# uc_ctrl.net
KiCad netlist of a schematic drawn in EAGLE
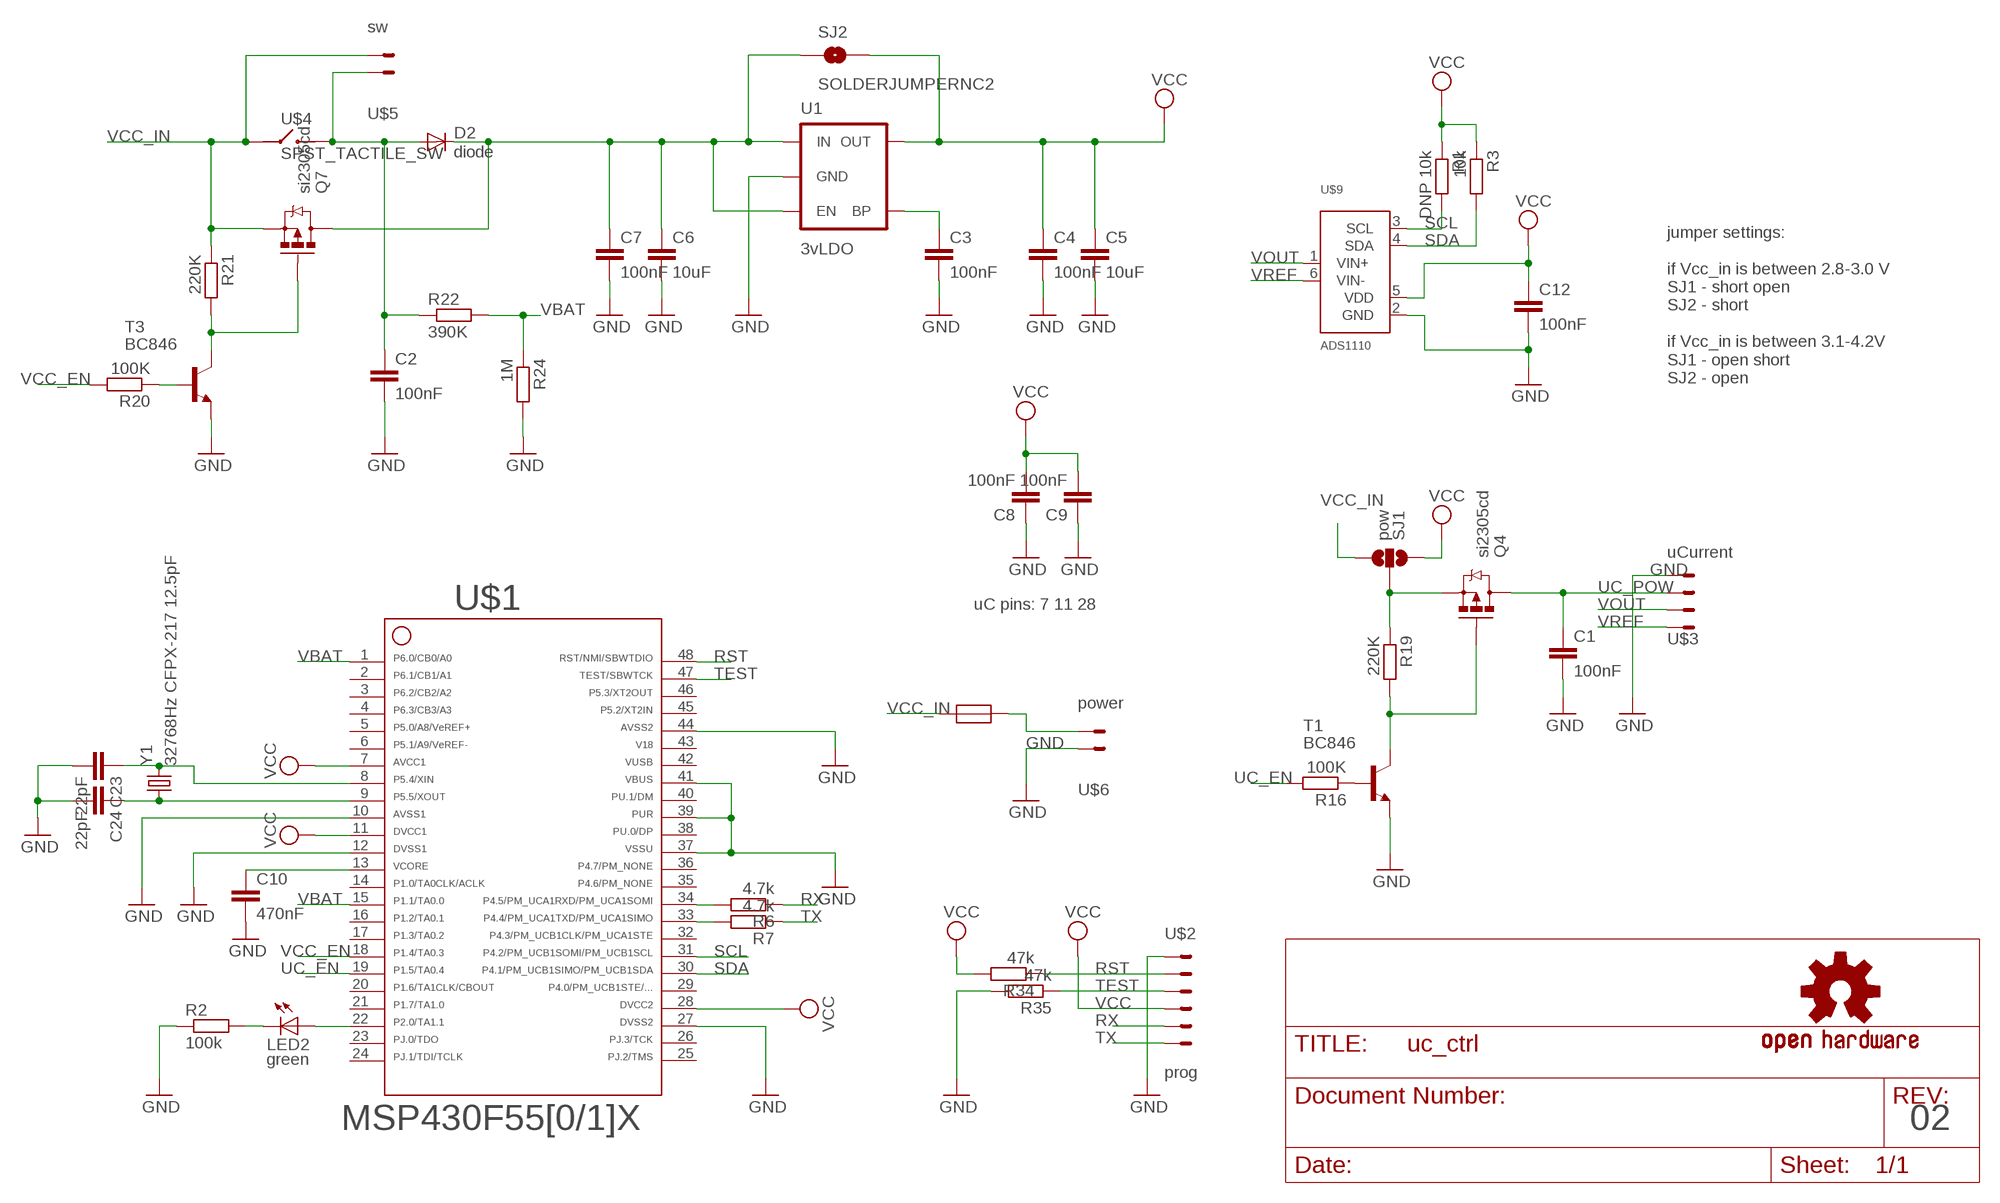
[diagram p0: schematic, sheet 1]

(export (version "E")
  (design (tool "Eeschema 10.0.6"))
  (components
    (comp (ref "C1")
      (value "100nF")
      (footprint "eagle-import:C0805")
      (libsource (lib "eagle-import") (part "C-EUC0805"))
    )
    (comp (ref "C2")
      (value "100nF")
      (footprint "eagle-import:C0805")
      (libsource (lib "eagle-import") (part "C-EUC0805"))
    )
    (comp (ref "C3")
      (value "100nF")
      (footprint "eagle-import:C0805")
      (libsource (lib "eagle-import") (part "C-EUC0805"))
    )
    (comp (ref "C4")
      (value "100nF")
      (footprint "eagle-import:C0805")
      (libsource (lib "eagle-import") (part "C-EUC0805"))
    )
    (comp (ref "C5")
      (value "10uF")
      (footprint "eagle-import:C0805")
      (libsource (lib "eagle-import") (part "C-EUC0805"))
    )
    (comp (ref "C6")
      (value "10uF")
      (footprint "eagle-import:C0805")
      (libsource (lib "eagle-import") (part "C-EUC0805"))
    )
    (comp (ref "C7")
      (value "100nF")
      (footprint "eagle-import:C0805")
      (libsource (lib "eagle-import") (part "C-EUC0805"))
    )
    (comp (ref "C8")
      (value "100nF")
      (footprint "eagle-import:C0805")
      (libsource (lib "eagle-import") (part "C-EUC0805"))
    )
    (comp (ref "C9")
      (value "100nF")
      (footprint "eagle-import:C0805")
      (libsource (lib "eagle-import") (part "C-EUC0805"))
    )
    (comp (ref "C10")
      (value "470nF")
      (footprint "eagle-import:C0805")
      (libsource (lib "eagle-import") (part "C-EUC0805"))
    )
    (comp (ref "C12")
      (value "100nF")
      (footprint "eagle-import:C0805")
      (libsource (lib "eagle-import") (part "C-EUC0805"))
    )
    (comp (ref "C23")
      (value "22pF")
      (footprint "eagle-import:C0805")
      (libsource (lib "eagle-import") (part "C-EUC0805"))
    )
    (comp (ref "C24")
      (value "22pF")
      (footprint "eagle-import:C0805")
      (libsource (lib "eagle-import") (part "C-EUC0805"))
    )
    (comp (ref "D2")
      (value "diode")
      (footprint "eagle-import:SMA-DIODE")
      (libsource (lib "eagle-import") (part "DIODESMA"))
    )
    (comp (ref "LED2")
      (value "green")
      (footprint "eagle-import:CHIPLED_0805")
      (libsource (lib "eagle-import") (part "LEDCHIPLED_0805"))
    )
    (comp (ref "Q4")
      (value "si2305cd")
      (footprint "eagle-import:SOT23-3_POWER")
      (libsource (lib "eagle-import") (part "MOSFET-PCHANNELSMD_POWER"))
    )
    (comp (ref "Q7")
      (value "si2305cd")
      (footprint "eagle-import:SOT23-3_POWER")
      (libsource (lib "eagle-import") (part "MOSFET-PCHANNELSMD_POWER"))
    )
    (comp (ref "R1")
      (value "DNP 10k")
      (footprint "eagle-import:R0805W")
      (libsource (lib "eagle-import") (part "R-EU_R0805W"))
    )
    (comp (ref "R2")
      (value "100k")
      (footprint "eagle-import:R0805W")
      (libsource (lib "eagle-import") (part "R-EU_R0805W"))
    )
    (comp (ref "R3")
      (value "10k")
      (footprint "eagle-import:R0805W")
      (libsource (lib "eagle-import") (part "R-EU_R0805W"))
    )
    (comp (ref "R6")
      (value "4.7k")
      (footprint "eagle-import:R0805W")
      (libsource (lib "eagle-import") (part "R-EU_R0805W"))
    )
    (comp (ref "R7")
      (value "4.7k")
      (footprint "eagle-import:R0805W")
      (libsource (lib "eagle-import") (part "R-EU_R0805W"))
    )
    (comp (ref "R16")
      (value "100K")
      (footprint "eagle-import:R0805W")
      (libsource (lib "eagle-import") (part "R-EU_R0805W"))
    )
    (comp (ref "R19")
      (value "220K")
      (footprint "eagle-import:R0805W")
      (libsource (lib "eagle-import") (part "R-EU_R0805W"))
    )
    (comp (ref "R20")
      (value "100K")
      (footprint "eagle-import:R0805W")
      (libsource (lib "eagle-import") (part "R-EU_R0805W"))
    )
    (comp (ref "R21")
      (value "220K")
      (footprint "eagle-import:R0805W")
      (libsource (lib "eagle-import") (part "R-EU_R0805W"))
    )
    (comp (ref "R22")
      (value "390K")
      (footprint "eagle-import:R0805W")
      (libsource (lib "eagle-import") (part "R-EU_R0805W"))
    )
    (comp (ref "R24")
      (value "1M")
      (footprint "eagle-import:R0805W")
      (libsource (lib "eagle-import") (part "R-EU_R0805W"))
    )
    (comp (ref "R34")
      (value "47k")
      (footprint "eagle-import:R0805W")
      (libsource (lib "eagle-import") (part "R-EU_R0805W"))
    )
    (comp (ref "R35")
      (value "47k")
      (footprint "eagle-import:R0805W")
      (libsource (lib "eagle-import") (part "R-EU_R0805W"))
    )
    (comp (ref "SJ1")
      (value "pow")
      (footprint "eagle-import:SJ_3_PASTE1&2")
      (libsource (lib "eagle-import") (part "SOLDERJUMPER_2WAYPASTE1&2"))
    )
    (comp (ref "SJ2")
      (value "SOLDERJUMPERNC2")
      (footprint "eagle-import:SJ_2S-NOTRACE")
      (libsource (lib "eagle-import") (part "SOLDERJUMPERNC2"))
    )
    (comp (ref "T1")
      (value "BC846")
      (footprint "eagle-import:SOT23")
      (libsource (lib "eagle-import") (part "BC846"))
    )
    (comp (ref "T3")
      (value "BC846")
      (footprint "eagle-import:SOT23")
      (libsource (lib "eagle-import") (part "BC846"))
    )
    (comp (ref "U$1")
      (value "F55[0/1]X---PT48")
      (footprint "eagle-import:PT48")
      (libsource (lib "eagle-import") (part "F55[0/1]X---PT48"))
    )
    (comp (ref "U$2")
      (value "prog")
      (footprint "eagle-import:0530480610")
      (libsource (lib "eagle-import") (part "MOLEX_6HORIZONTAL"))
    )
    (comp (ref "U$3")
      (value "uCurrent")
      (footprint "eagle-import:0530480401")
      (libsource (lib "eagle-import") (part "MOLEX_4HORIZONTAL"))
    )
    (comp (ref "U$4")
      (value "SPST_TACTILE_SW")
      (footprint "eagle-import:6X3.5_TACTILE_SW")
      (libsource (lib "eagle-import") (part "SPST_TACTILE_SW"))
    )
    (comp (ref "U$5")
      (value "sw")
      (footprint "eagle-import:0530480210")
      (libsource (lib "eagle-import") (part "MOLEX_2HORIZONTAL"))
    )
    (comp (ref "U$6")
      (value "power")
      (footprint "eagle-import:0530480210")
      (libsource (lib "eagle-import") (part "MOLEX_2HORIZONTAL"))
    )
    (comp (ref "U$7")
      (value "OSHW-LOGOM")
      (footprint "eagle-import:OSHW-LOGO-M")
      (libsource (lib "eagle-import") (part "OSHW-LOGOM"))
    )
    (comp (ref "U$8")
      (value "RESETTABLE")
      (footprint "eagle-import:1210")
      (libsource (lib "eagle-import") (part "RESETTABLE"))
    )
    (comp (ref "U$9")
      (value "ADS1110")
      (footprint "eagle-import:SOT23-6")
      (libsource (lib "eagle-import") (part "ADS1110"))
    )
    (comp (ref "U1")
      (value "3vLDO")
      (footprint "eagle-import:SOT23-5")
      (libsource (lib "eagle-import") (part "V_REG_LDOSMD"))
    )
    (comp (ref "Y1")
      (value "32768Hz CFPX-217 12.5pF")
      (footprint "eagle-import:CRYSTAL-SMD-3.2X1.5")
      (libsource (lib "eagle-import") (part "CRYSTAL3.2X1.5"))
    )
  )
  (nets
    (net (code "1") (name "/42") (class "Default")
      (node (ref "U$1") (pin "42") (pinfunction "42_42") (pintype "power_in"))
    )
    (net (code "2") (name "/43") (class "Default")
      (node (ref "U$1") (pin "43") (pinfunction "43_43") (pintype "power_in"))
    )
    (net (code "3") (name "/46") (class "Default")
      (node (ref "U$1") (pin "46") (pinfunction "46_46") (pintype "power_in"))
    )
    (net (code "4") (name "/RST") (class "Default")
      (node (ref "R34") (pin "1") (pinfunction "1_1") (pintype "passive"))
      (node (ref "U$1") (pin "48") (pinfunction "48_48") (pintype "bidirectional"))
      (node (ref "U$2") (pin "2") (pinfunction "2_2") (pintype "passive"))
    )
    (net (code "5") (name "/RX") (class "Default")
      (node (ref "R6") (pin "1") (pinfunction "1_1") (pintype "passive"))
      (node (ref "U$2") (pin "5") (pinfunction "5_5") (pintype "passive"))
    )
    (net (code "6") (name "/SCL") (class "Default")
      (node (ref "R1") (pin "2") (pinfunction "2_2") (pintype "passive"))
      (node (ref "U$1") (pin "31") (pinfunction "31_31") (pintype "bidirectional"))
      (node (ref "U$9") (pin "3") (pinfunction "SCL_3") (pintype "bidirectional"))
    )
    (net (code "7") (name "/SDA") (class "Default")
      (node (ref "R3") (pin "2") (pinfunction "2_2") (pintype "passive"))
      (node (ref "U$1") (pin "30") (pinfunction "30_30") (pintype "bidirectional"))
      (node (ref "U$9") (pin "4") (pinfunction "SDA_4") (pintype "bidirectional"))
    )
    (net (code "8") (name "/TEST") (class "Default")
      (node (ref "R35") (pin "1") (pinfunction "1_1") (pintype "passive"))
      (node (ref "U$1") (pin "47") (pinfunction "47_47") (pintype "input"))
      (node (ref "U$2") (pin "3") (pinfunction "3_3") (pintype "passive"))
    )
    (net (code "9") (name "/TX") (class "Default")
      (node (ref "R7") (pin "1") (pinfunction "1_1") (pintype "passive"))
      (node (ref "U$2") (pin "6") (pinfunction "6_6") (pintype "passive"))
    )
    (net (code "10") (name "/UC_EN") (class "Default")
      (node (ref "R16") (pin "2") (pinfunction "2_2") (pintype "passive"))
      (node (ref "U$1") (pin "19") (pinfunction "19_19") (pintype "bidirectional"))
    )
    (net (code "11") (name "/UC_POW") (class "Default")
      (node (ref "C1") (pin "1") (pinfunction "1_1") (pintype "passive"))
      (node (ref "Q4") (pin "3") (pinfunction "D_3") (pintype "passive"))
      (node (ref "U$3") (pin "2") (pinfunction "2_2") (pintype "passive"))
    )
    (net (code "12") (name "/VBAT") (class "Default")
      (node (ref "R22") (pin "2") (pinfunction "2_2") (pintype "passive"))
      (node (ref "R24") (pin "1") (pinfunction "1_1") (pintype "passive"))
      (node (ref "U$1") (pin "1") (pinfunction "1_1") (pintype "bidirectional"))
      (node (ref "U$1") (pin "15") (pinfunction "15_15") (pintype "bidirectional"))
    )
    (net (code "13") (name "/VCC_EN") (class "Default")
      (node (ref "R20") (pin "2") (pinfunction "2_2") (pintype "passive"))
      (node (ref "U$1") (pin "18") (pinfunction "18_18") (pintype "bidirectional"))
    )
    (net (code "14") (name "/VCC_IN") (class "Default")
      (node (ref "Q7") (pin "2") (pinfunction "S_2") (pintype "passive"))
      (node (ref "R21") (pin "1") (pinfunction "1_1") (pintype "passive"))
      (node (ref "SJ1") (pin "3") (pinfunction "3_3") (pintype "passive"))
      (node (ref "U$4") (pin "1") (pinfunction "1_1") (pintype "passive"))
      (node (ref "U$5") (pin "P$2") (pinfunction "2_P$2") (pintype "passive"))
      (node (ref "U$8") (pin "P$1") (pinfunction "P$1_P$1") (pintype "bidirectional"))
    )
    (net (code "15") (name "/VOUT") (class "Default")
      (node (ref "U$3") (pin "3") (pinfunction "3_3") (pintype "passive"))
      (node (ref "U$9") (pin "1") (pinfunction "VIN+_1") (pintype "input"))
    )
    (net (code "16") (name "/VREF") (class "Default")
      (node (ref "U$3") (pin "4") (pinfunction "4_4") (pintype "passive"))
      (node (ref "U$9") (pin "6") (pinfunction "VIN-_6") (pintype "input"))
    )
    (net (code "17") (name "GND") (class "Default")
      (node (ref "C1") (pin "2") (pinfunction "2_2") (pintype "passive"))
      (node (ref "C10") (pin "2") (pinfunction "2_2") (pintype "passive"))
      (node (ref "C12") (pin "2") (pinfunction "2_2") (pintype "passive"))
      (node (ref "C2") (pin "2") (pinfunction "2_2") (pintype "passive"))
      (node (ref "C23") (pin "2") (pinfunction "2_2") (pintype "passive"))
      (node (ref "C24") (pin "2") (pinfunction "2_2") (pintype "passive"))
      (node (ref "C3") (pin "2") (pinfunction "2_2") (pintype "passive"))
      (node (ref "C4") (pin "2") (pinfunction "2_2") (pintype "passive"))
      (node (ref "C5") (pin "2") (pinfunction "2_2") (pintype "passive"))
      (node (ref "C6") (pin "2") (pinfunction "2_2") (pintype "passive"))
      (node (ref "C7") (pin "2") (pinfunction "2_2") (pintype "passive"))
      (node (ref "C8") (pin "1") (pinfunction "1_1") (pintype "passive"))
      (node (ref "C9") (pin "1") (pinfunction "1_1") (pintype "passive"))
      (node (ref "R2") (pin "1") (pinfunction "1_1") (pintype "passive"))
      (node (ref "R24") (pin "2") (pinfunction "2_2") (pintype "passive"))
      (node (ref "R35") (pin "2") (pinfunction "2_2") (pintype "passive"))
      (node (ref "T1") (pin "2") (pinfunction "E_2") (pintype "passive"))
      (node (ref "T3") (pin "2") (pinfunction "E_2") (pintype "passive"))
      (node (ref "U$1") (pin "10") (pinfunction "10_10") (pintype "power_in"))
      (node (ref "U$1") (pin "12") (pinfunction "12_12") (pintype "power_in"))
      (node (ref "U$1") (pin "27") (pinfunction "27_27") (pintype "power_in"))
      (node (ref "U$1") (pin "37") (pinfunction "37_37") (pintype "power_in"))
      (node (ref "U$1") (pin "39") (pinfunction "39_39") (pintype "bidirectional"))
      (node (ref "U$1") (pin "41") (pinfunction "41_41") (pintype "power_in"))
      (node (ref "U$1") (pin "44") (pinfunction "44_44") (pintype "power_in"))
      (node (ref "U$2") (pin "1") (pinfunction "1_1") (pintype "passive"))
      (node (ref "U$3") (pin "1") (pinfunction "1_1") (pintype "passive"))
      (node (ref "U$6") (pin "P$1") (pinfunction "1_P$1") (pintype "passive"))
      (node (ref "U$9") (pin "2") (pinfunction "GND_2") (pintype "power_in"))
      (node (ref "U1") (pin "2") (pinfunction "GND_2") (pintype "input"))
    )
    (net (code "18") (name "Net-(C10-Pad1)") (class "Default")
      (node (ref "C10") (pin "1") (pinfunction "1_1") (pintype "passive"))
      (node (ref "U$1") (pin "13") (pinfunction "13_13") (pintype "power_in"))
    )
    (net (code "19") (name "Net-(LED2-PadA)") (class "Default")
      (node (ref "LED2") (pin "A") (pinfunction "A_A") (pintype "passive"))
      (node (ref "U$1") (pin "22") (pinfunction "22_22") (pintype "bidirectional"))
    )
    (net (code "20") (name "Net-(LED2-PadC)") (class "Default")
      (node (ref "LED2") (pin "C") (pinfunction "C_C") (pintype "passive"))
      (node (ref "R2") (pin "2") (pinfunction "2_2") (pintype "passive"))
    )
    (net (code "21") (name "Net-(Q4-G)") (class "Default")
      (node (ref "Q4") (pin "1") (pinfunction "G_1") (pintype "passive"))
      (node (ref "R19") (pin "2") (pinfunction "2_2") (pintype "passive"))
      (node (ref "T1") (pin "3") (pinfunction "C_3") (pintype "passive"))
    )
    (net (code "22") (name "Net-(Q4-S)") (class "Default")
      (node (ref "Q4") (pin "2") (pinfunction "S_2") (pintype "passive"))
      (node (ref "R19") (pin "1") (pinfunction "1_1") (pintype "passive"))
      (node (ref "SJ1") (pin "2") (pinfunction "2_2") (pintype "passive"))
    )
    (net (code "23") (name "Net-(Q7-D)") (class "Default")
      (node (ref "C6") (pin "1") (pinfunction "1_1") (pintype "passive"))
      (node (ref "C7") (pin "1") (pinfunction "1_1") (pintype "passive"))
      (node (ref "D2") (pin "C") (pinfunction "C_C") (pintype "passive"))
      (node (ref "Q7") (pin "3") (pinfunction "D_3") (pintype "passive"))
      (node (ref "SJ2") (pin "1") (pinfunction "1_1") (pintype "passive"))
      (node (ref "U1") (pin "1") (pinfunction "IN_1") (pintype "input"))
      (node (ref "U1") (pin "3") (pinfunction "EN_3") (pintype "input"))
    )
    (net (code "24") (name "Net-(Q7-G)") (class "Default")
      (node (ref "Q7") (pin "1") (pinfunction "G_1") (pintype "passive"))
      (node (ref "R21") (pin "2") (pinfunction "2_2") (pintype "passive"))
      (node (ref "T3") (pin "3") (pinfunction "C_3") (pintype "passive"))
    )
    (net (code "25") (name "Net-(R6-Pad2)") (class "Default")
      (node (ref "R6") (pin "2") (pinfunction "2_2") (pintype "passive"))
      (node (ref "U$1") (pin "34") (pinfunction "34_34") (pintype "bidirectional"))
    )
    (net (code "26") (name "Net-(R7-Pad2)") (class "Default")
      (node (ref "R7") (pin "2") (pinfunction "2_2") (pintype "passive"))
      (node (ref "U$1") (pin "33") (pinfunction "33_33") (pintype "bidirectional"))
    )
    (net (code "27") (name "Net-(T1-B)") (class "Default")
      (node (ref "R16") (pin "1") (pinfunction "1_1") (pintype "passive"))
      (node (ref "T1") (pin "1") (pinfunction "B_1") (pintype "passive"))
    )
    (net (code "28") (name "Net-(T3-B)") (class "Default")
      (node (ref "R20") (pin "1") (pinfunction "1_1") (pintype "passive"))
      (node (ref "T3") (pin "1") (pinfunction "B_1") (pintype "passive"))
    )
    (net (code "29") (name "Net-(U$5-1)") (class "Default")
      (node (ref "C2") (pin "1") (pinfunction "1_1") (pintype "passive"))
      (node (ref "D2") (pin "A") (pinfunction "A_A") (pintype "passive"))
      (node (ref "R22") (pin "1") (pinfunction "1_1") (pintype "passive"))
      (node (ref "U$4") (pin "2") (pinfunction "2_2") (pintype "passive"))
      (node (ref "U$5") (pin "P$1") (pinfunction "1_P$1") (pintype "passive"))
    )
    (net (code "30") (name "Net-(U$6-2)") (class "Default")
      (node (ref "U$6") (pin "P$2") (pinfunction "2_P$2") (pintype "passive"))
      (node (ref "U$8") (pin "P$2") (pinfunction "P$2_P$2") (pintype "bidirectional"))
    )
    (net (code "31") (name "Net-(U1-BP)") (class "Default")
      (node (ref "C3") (pin "1") (pinfunction "1_1") (pintype "passive"))
      (node (ref "U1") (pin "4") (pinfunction "BP_4") (pintype "input"))
    )
    (net (code "32") (name "Net-(Y1-1)") (class "Default")
      (node (ref "C24") (pin "1") (pinfunction "1_1") (pintype "passive"))
      (node (ref "U$1") (pin "9") (pinfunction "9_9") (pintype "bidirectional"))
      (node (ref "Y1") (pin "P$1") (pinfunction "1_P$1") (pintype "passive"))
    )
    (net (code "33") (name "Net-(Y1-2)") (class "Default")
      (node (ref "C23") (pin "1") (pinfunction "1_1") (pintype "passive"))
      (node (ref "U$1") (pin "8") (pinfunction "8_8") (pintype "bidirectional"))
      (node (ref "Y1") (pin "P$2") (pinfunction "2_P$2") (pintype "passive"))
    )
    (net (code "34") (name "VCC") (class "Default")
      (node (ref "C12") (pin "1") (pinfunction "1_1") (pintype "passive"))
      (node (ref "C4") (pin "1") (pinfunction "1_1") (pintype "passive"))
      (node (ref "C5") (pin "1") (pinfunction "1_1") (pintype "passive"))
      (node (ref "C8") (pin "2") (pinfunction "2_2") (pintype "passive"))
      (node (ref "C9") (pin "2") (pinfunction "2_2") (pintype "passive"))
      (node (ref "R1") (pin "1") (pinfunction "1_1") (pintype "passive"))
      (node (ref "R3") (pin "1") (pinfunction "1_1") (pintype "passive"))
      (node (ref "R34") (pin "2") (pinfunction "2_2") (pintype "passive"))
      (node (ref "SJ1") (pin "1") (pinfunction "1_1") (pintype "passive"))
      (node (ref "SJ2") (pin "2") (pinfunction "2_2") (pintype "passive"))
      (node (ref "U$1") (pin "11") (pinfunction "11_11") (pintype "power_in"))
      (node (ref "U$1") (pin "28") (pinfunction "28_28") (pintype "power_in"))
      (node (ref "U$1") (pin "7") (pinfunction "7_7") (pintype "power_in"))
      (node (ref "U$2") (pin "4") (pinfunction "4_4") (pintype "passive"))
      (node (ref "U$9") (pin "5") (pinfunction "VDD_5") (pintype "power_in"))
      (node (ref "U1") (pin "5") (pinfunction "OUT_5") (pintype "passive"))
    )
    (net (code "35") (name "unconnected-(U$1-Pad2)") (class "Default")
      (node (ref "U$1") (pin "2") (pinfunction "2_2") (pintype "bidirectional"))
    )
    (net (code "36") (name "unconnected-(U$1-Pad3)") (class "Default")
      (node (ref "U$1") (pin "3") (pinfunction "3_3") (pintype "bidirectional"))
    )
    (net (code "37") (name "unconnected-(U$1-Pad4)") (class "Default")
      (node (ref "U$1") (pin "4") (pinfunction "4_4") (pintype "bidirectional"))
    )
    (net (code "38") (name "unconnected-(U$1-Pad5)") (class "Default")
      (node (ref "U$1") (pin "5") (pinfunction "5_5") (pintype "bidirectional"))
    )
    (net (code "39") (name "unconnected-(U$1-Pad6)") (class "Default")
      (node (ref "U$1") (pin "6") (pinfunction "6_6") (pintype "bidirectional"))
    )
    (net (code "40") (name "unconnected-(U$1-Pad14)") (class "Default")
      (node (ref "U$1") (pin "14") (pinfunction "14_14") (pintype "bidirectional"))
    )
    (net (code "41") (name "unconnected-(U$1-Pad16)") (class "Default")
      (node (ref "U$1") (pin "16") (pinfunction "16_16") (pintype "bidirectional"))
    )
    (net (code "42") (name "unconnected-(U$1-Pad17)") (class "Default")
      (node (ref "U$1") (pin "17") (pinfunction "17_17") (pintype "bidirectional"))
    )
    (net (code "43") (name "unconnected-(U$1-Pad20)") (class "Default")
      (node (ref "U$1") (pin "20") (pinfunction "20_20") (pintype "bidirectional"))
    )
    (net (code "44") (name "unconnected-(U$1-Pad21)") (class "Default")
      (node (ref "U$1") (pin "21") (pinfunction "21_21") (pintype "bidirectional"))
    )
    (net (code "45") (name "unconnected-(U$1-Pad23)") (class "Default")
      (node (ref "U$1") (pin "23") (pinfunction "23_23") (pintype "bidirectional"))
    )
    (net (code "46") (name "unconnected-(U$1-Pad24)") (class "Default")
      (node (ref "U$1") (pin "24") (pinfunction "24_24") (pintype "bidirectional"))
    )
    (net (code "47") (name "unconnected-(U$1-Pad25)") (class "Default")
      (node (ref "U$1") (pin "25") (pinfunction "25_25") (pintype "bidirectional"))
    )
    (net (code "48") (name "unconnected-(U$1-Pad26)") (class "Default")
      (node (ref "U$1") (pin "26") (pinfunction "26_26") (pintype "bidirectional"))
    )
    (net (code "49") (name "unconnected-(U$1-Pad29)") (class "Default")
      (node (ref "U$1") (pin "29") (pinfunction "29_29") (pintype "bidirectional"))
    )
    (net (code "50") (name "unconnected-(U$1-Pad32)") (class "Default")
      (node (ref "U$1") (pin "32") (pinfunction "32_32") (pintype "bidirectional"))
    )
    (net (code "51") (name "unconnected-(U$1-Pad35)") (class "Default")
      (node (ref "U$1") (pin "35") (pinfunction "35_35") (pintype "bidirectional"))
    )
    (net (code "52") (name "unconnected-(U$1-Pad36)") (class "Default")
      (node (ref "U$1") (pin "36") (pinfunction "36_36") (pintype "bidirectional"))
    )
    (net (code "53") (name "unconnected-(U$1-Pad38)") (class "Default")
      (node (ref "U$1") (pin "38") (pinfunction "38_38") (pintype "bidirectional"))
    )
    (net (code "54") (name "unconnected-(U$1-Pad40)") (class "Default")
      (node (ref "U$1") (pin "40") (pinfunction "40_40") (pintype "bidirectional"))
    )
    (net (code "55") (name "unconnected-(U$1-Pad45)") (class "Default")
      (node (ref "U$1") (pin "45") (pinfunction "45_45") (pintype "bidirectional"))
    )
  )
)
